# ControllerESP32.net
KiCad netlist of a schematic drawn in EAGLE
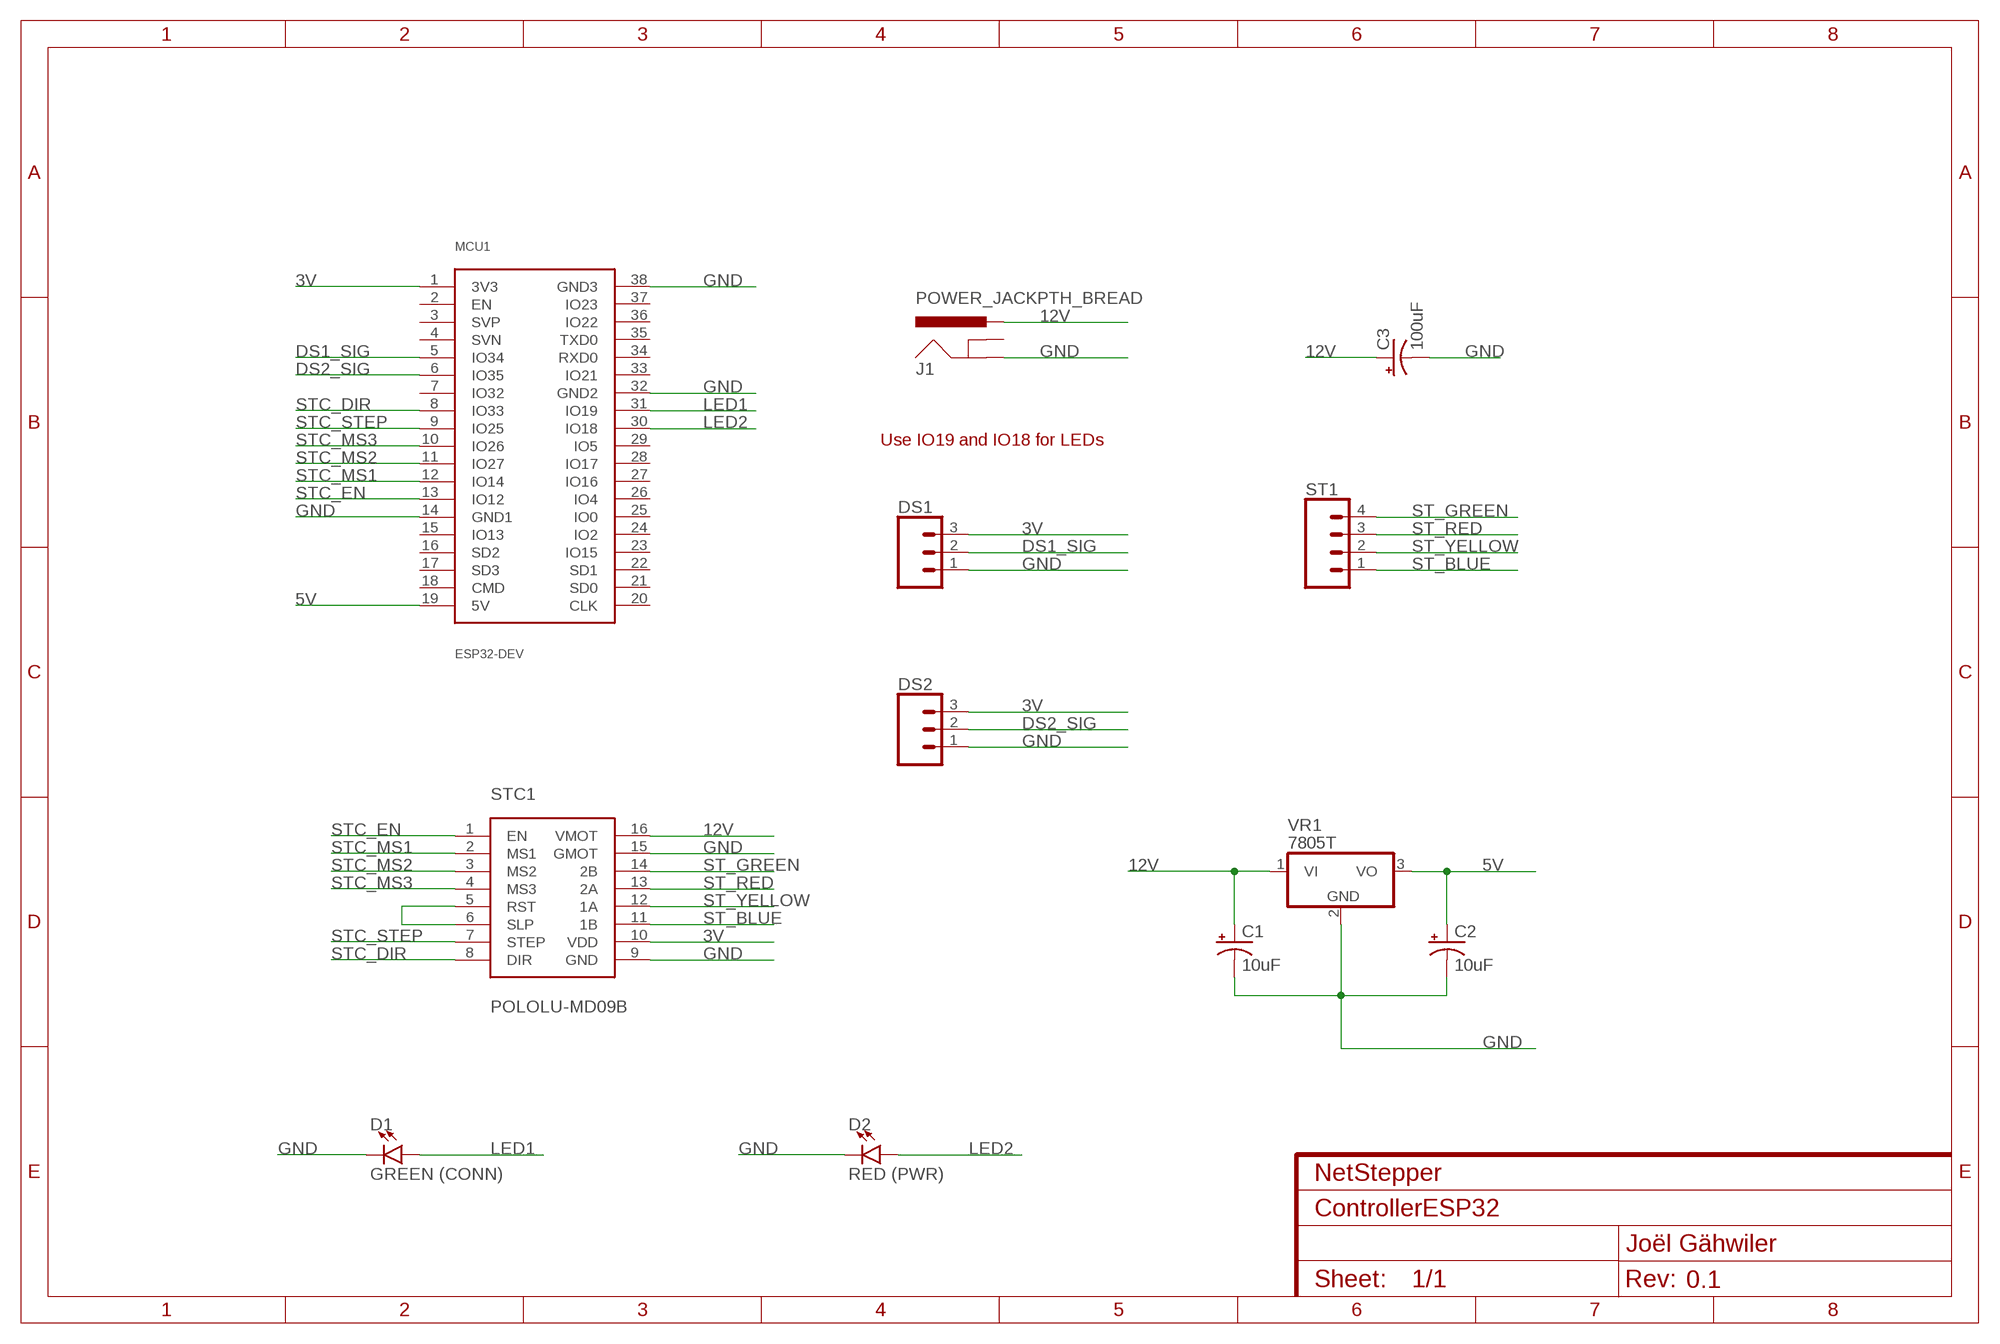
[diagram p0: schematic, sheet 1]

(export (version "E")
  (design (tool "Eeschema 10.0.6"))
  (components
    (comp (ref "C1")
      (value "10uF")
      (footprint "eagle-import:E2-5")
      (libsource (lib "eagle-import") (part "CPOL-USE2-5"))
    )
    (comp (ref "C2")
      (value "10uF")
      (footprint "eagle-import:E2-5")
      (libsource (lib "eagle-import") (part "CPOL-USE2-5"))
    )
    (comp (ref "C3")
      (value "100uF")
      (footprint "eagle-import:E2-5")
      (libsource (lib "eagle-import") (part "CPOL-USE2-5"))
    )
    (comp (ref "D1")
      (value "GREEN (CONN)")
      (footprint "eagle-import:LED_5MM")
      (libsource (lib "eagle-import") (part "LED5MM"))
    )
    (comp (ref "D2")
      (value "RED (PWR)")
      (footprint "eagle-import:LED_5MM")
      (libsource (lib "eagle-import") (part "LED5MM"))
    )
    (comp (ref "DS1")
      (value "CONN_03LONGPADS")
      (footprint "eagle-import:1X03_LONGPADS")
      (libsource (lib "eagle-import") (part "CONN_03LONGPADS"))
    )
    (comp (ref "DS2")
      (value "CONN_03LONGPADS")
      (footprint "eagle-import:1X03_LONGPADS")
      (libsource (lib "eagle-import") (part "CONN_03LONGPADS"))
    )
    (comp (ref "J1")
      (value "POWER_JACKPTH_BREAD")
      (footprint "eagle-import:POWER_JACK_PTH_BREAD")
      (libsource (lib "eagle-import") (part "POWER_JACKPTH_BREAD"))
    )
    (comp (ref "MCU1")
      (value "ESP32-DEV")
      (footprint "eagle-import:ESP32-DEV")
      (libsource (lib "eagle-import") (part "ESP32-DEV"))
    )
    (comp (ref "ST1")
      (value "CONN_04LONGPADS")
      (footprint "eagle-import:1X04_LONGPADS")
      (libsource (lib "eagle-import") (part "CONN_04LONGPADS"))
    )
    (comp (ref "STC1")
      (value "POLOLU-MD09B")
      (footprint "eagle-import:POLOLU-MD09B")
      (libsource (lib "eagle-import") (part "POLOLU-MD09B"))
    )
    (comp (ref "VR1")
      (value "7805T")
      (footprint "eagle-import:TO220H")
      (libsource (lib "eagle-import") (part "78T05"))
    )
  )
  (nets
    (net (code "1") (name "/3V") (class "Default")
      (node (ref "DS1") (pin "3") (pinfunction "3_3") (pintype "passive"))
      (node (ref "DS2") (pin "3") (pinfunction "3_3") (pintype "passive"))
      (node (ref "MCU1") (pin "1") (pinfunction "3V3_1") (pintype "bidirectional"))
      (node (ref "STC1") (pin "10") (pinfunction "VDD_10") (pintype "bidirectional"))
    )
    (net (code "2") (name "/5V") (class "Default")
      (node (ref "C2") (pin "+") (pinfunction "+_+") (pintype "passive"))
      (node (ref "MCU1") (pin "19") (pinfunction "5V_19") (pintype "bidirectional"))
      (node (ref "VR1") (pin "3") (pinfunction "VO_3") (pintype "passive"))
    )
    (net (code "3") (name "/12V") (class "Default")
      (node (ref "C1") (pin "+") (pinfunction "+_+") (pintype "passive"))
      (node (ref "C3") (pin "+") (pinfunction "+_+") (pintype "passive"))
      (node (ref "J1") (pin "PWR") (pinfunction "PWR_PWR") (pintype "bidirectional"))
      (node (ref "STC1") (pin "16") (pinfunction "VMOT_16") (pintype "bidirectional"))
      (node (ref "VR1") (pin "1") (pinfunction "VI_1") (pintype "input"))
    )
    (net (code "4") (name "/DS1_SIG") (class "Default")
      (node (ref "DS1") (pin "2") (pinfunction "2_2") (pintype "passive"))
      (node (ref "MCU1") (pin "5") (pinfunction "IO34_5") (pintype "bidirectional"))
    )
    (net (code "5") (name "/DS2_SIG") (class "Default")
      (node (ref "DS2") (pin "2") (pinfunction "2_2") (pintype "passive"))
      (node (ref "MCU1") (pin "6") (pinfunction "IO35_6") (pintype "bidirectional"))
    )
    (net (code "6") (name "/GND") (class "Default")
      (node (ref "C1") (pin "-") (pinfunction "-_-") (pintype "passive"))
      (node (ref "C2") (pin "-") (pinfunction "-_-") (pintype "passive"))
      (node (ref "C3") (pin "-") (pinfunction "-_-") (pintype "passive"))
      (node (ref "D1") (pin "K") (pinfunction "C_K") (pintype "passive"))
      (node (ref "D2") (pin "K") (pinfunction "C_K") (pintype "passive"))
      (node (ref "DS1") (pin "1") (pinfunction "1_1") (pintype "passive"))
      (node (ref "DS2") (pin "1") (pinfunction "1_1") (pintype "passive"))
      (node (ref "J1") (pin "GND") (pinfunction "GND_GND") (pintype "bidirectional"))
      (node (ref "MCU1") (pin "14") (pinfunction "GND1_14") (pintype "bidirectional"))
      (node (ref "MCU1") (pin "32") (pinfunction "GND2_32") (pintype "bidirectional"))
      (node (ref "MCU1") (pin "38") (pinfunction "GND3_38") (pintype "bidirectional"))
      (node (ref "STC1") (pin "15") (pinfunction "GMOT_15") (pintype "bidirectional"))
      (node (ref "STC1") (pin "9") (pinfunction "GND_9") (pintype "bidirectional"))
      (node (ref "VR1") (pin "2") (pinfunction "GND_2") (pintype "passive"))
    )
    (net (code "7") (name "/LED1") (class "Default")
      (node (ref "D1") (pin "A") (pinfunction "A_A") (pintype "passive"))
      (node (ref "MCU1") (pin "31") (pinfunction "IO19_31") (pintype "bidirectional"))
    )
    (net (code "8") (name "/LED2") (class "Default")
      (node (ref "D2") (pin "A") (pinfunction "A_A") (pintype "passive"))
      (node (ref "MCU1") (pin "30") (pinfunction "IO18_30") (pintype "bidirectional"))
    )
    (net (code "9") (name "/STC_DIR") (class "Default")
      (node (ref "MCU1") (pin "8") (pinfunction "IO33_8") (pintype "bidirectional"))
      (node (ref "STC1") (pin "8") (pinfunction "DIR_8") (pintype "bidirectional"))
    )
    (net (code "10") (name "/STC_EN") (class "Default")
      (node (ref "MCU1") (pin "13") (pinfunction "IO12_13") (pintype "bidirectional"))
      (node (ref "STC1") (pin "1") (pinfunction "EN_1") (pintype "bidirectional"))
    )
    (net (code "11") (name "/STC_MS1") (class "Default")
      (node (ref "MCU1") (pin "12") (pinfunction "IO14_12") (pintype "bidirectional"))
      (node (ref "STC1") (pin "2") (pinfunction "MS1_2") (pintype "bidirectional"))
    )
    (net (code "12") (name "/STC_MS2") (class "Default")
      (node (ref "MCU1") (pin "11") (pinfunction "IO27_11") (pintype "bidirectional"))
      (node (ref "STC1") (pin "3") (pinfunction "MS2_3") (pintype "bidirectional"))
    )
    (net (code "13") (name "/STC_MS3") (class "Default")
      (node (ref "MCU1") (pin "10") (pinfunction "IO26_10") (pintype "bidirectional"))
      (node (ref "STC1") (pin "4") (pinfunction "MS3_4") (pintype "bidirectional"))
    )
    (net (code "14") (name "/STC_STEP") (class "Default")
      (node (ref "MCU1") (pin "9") (pinfunction "IO25_9") (pintype "bidirectional"))
      (node (ref "STC1") (pin "7") (pinfunction "STEP_7") (pintype "bidirectional"))
    )
    (net (code "15") (name "/ST_BLUE") (class "Default")
      (node (ref "ST1") (pin "1") (pinfunction "1_1") (pintype "passive"))
      (node (ref "STC1") (pin "11") (pinfunction "1B_11") (pintype "bidirectional"))
    )
    (net (code "16") (name "/ST_GREEN") (class "Default")
      (node (ref "ST1") (pin "4") (pinfunction "4_4") (pintype "passive"))
      (node (ref "STC1") (pin "14") (pinfunction "2B_14") (pintype "bidirectional"))
    )
    (net (code "17") (name "/ST_RED") (class "Default")
      (node (ref "ST1") (pin "3") (pinfunction "3_3") (pintype "passive"))
      (node (ref "STC1") (pin "13") (pinfunction "2A_13") (pintype "bidirectional"))
    )
    (net (code "18") (name "/ST_YELLOW") (class "Default")
      (node (ref "ST1") (pin "2") (pinfunction "2_2") (pintype "passive"))
      (node (ref "STC1") (pin "12") (pinfunction "1A_12") (pintype "bidirectional"))
    )
    (net (code "19") (name "Net-(STC1-RST)") (class "Default")
      (node (ref "STC1") (pin "5") (pinfunction "RST_5") (pintype "bidirectional"))
      (node (ref "STC1") (pin "6") (pinfunction "SLP_6") (pintype "bidirectional"))
    )
    (net (code "20") (name "unconnected-(J1-PadGNDBREAK)") (class "Default")
      (node (ref "J1") (pin "GNDBREAK") (pinfunction "GNDBREAK_GNDBREAK") (pintype "bidirectional"))
    )
    (net (code "21") (name "unconnected-(MCU1-CLK-Pad20)") (class "Default")
      (node (ref "MCU1") (pin "20") (pinfunction "CLK_20") (pintype "bidirectional"))
    )
    (net (code "22") (name "unconnected-(MCU1-CMD-Pad18)") (class "Default")
      (node (ref "MCU1") (pin "18") (pinfunction "CMD_18") (pintype "bidirectional"))
    )
    (net (code "23") (name "unconnected-(MCU1-EN-Pad2)") (class "Default")
      (node (ref "MCU1") (pin "2") (pinfunction "EN_2") (pintype "bidirectional"))
    )
    (net (code "24") (name "unconnected-(MCU1-IO0-Pad25)") (class "Default")
      (node (ref "MCU1") (pin "25") (pinfunction "IO0_25") (pintype "bidirectional"))
    )
    (net (code "25") (name "unconnected-(MCU1-IO2-Pad24)") (class "Default")
      (node (ref "MCU1") (pin "24") (pinfunction "IO2_24") (pintype "bidirectional"))
    )
    (net (code "26") (name "unconnected-(MCU1-IO4-Pad26)") (class "Default")
      (node (ref "MCU1") (pin "26") (pinfunction "IO4_26") (pintype "bidirectional"))
    )
    (net (code "27") (name "unconnected-(MCU1-IO5-Pad29)") (class "Default")
      (node (ref "MCU1") (pin "29") (pinfunction "IO5_29") (pintype "bidirectional"))
    )
    (net (code "28") (name "unconnected-(MCU1-IO13-Pad15)") (class "Default")
      (node (ref "MCU1") (pin "15") (pinfunction "IO13_15") (pintype "bidirectional"))
    )
    (net (code "29") (name "unconnected-(MCU1-IO15-Pad23)") (class "Default")
      (node (ref "MCU1") (pin "23") (pinfunction "IO15_23") (pintype "bidirectional"))
    )
    (net (code "30") (name "unconnected-(MCU1-IO16-Pad27)") (class "Default")
      (node (ref "MCU1") (pin "27") (pinfunction "IO16_27") (pintype "bidirectional"))
    )
    (net (code "31") (name "unconnected-(MCU1-IO17-Pad28)") (class "Default")
      (node (ref "MCU1") (pin "28") (pinfunction "IO17_28") (pintype "bidirectional"))
    )
    (net (code "32") (name "unconnected-(MCU1-IO21-Pad33)") (class "Default")
      (node (ref "MCU1") (pin "33") (pinfunction "IO21_33") (pintype "bidirectional"))
    )
    (net (code "33") (name "unconnected-(MCU1-IO22-Pad36)") (class "Default")
      (node (ref "MCU1") (pin "36") (pinfunction "IO22_36") (pintype "bidirectional"))
    )
    (net (code "34") (name "unconnected-(MCU1-IO23-Pad37)") (class "Default")
      (node (ref "MCU1") (pin "37") (pinfunction "IO23_37") (pintype "bidirectional"))
    )
    (net (code "35") (name "unconnected-(MCU1-IO32-Pad7)") (class "Default")
      (node (ref "MCU1") (pin "7") (pinfunction "IO32_7") (pintype "bidirectional"))
    )
    (net (code "36") (name "unconnected-(MCU1-RXD0-Pad34)") (class "Default")
      (node (ref "MCU1") (pin "34") (pinfunction "RXD0_34") (pintype "bidirectional"))
    )
    (net (code "37") (name "unconnected-(MCU1-SD0-Pad21)") (class "Default")
      (node (ref "MCU1") (pin "21") (pinfunction "SD0_21") (pintype "bidirectional"))
    )
    (net (code "38") (name "unconnected-(MCU1-SD1-Pad22)") (class "Default")
      (node (ref "MCU1") (pin "22") (pinfunction "SD1_22") (pintype "bidirectional"))
    )
    (net (code "39") (name "unconnected-(MCU1-SD2-Pad16)") (class "Default")
      (node (ref "MCU1") (pin "16") (pinfunction "SD2_16") (pintype "bidirectional"))
    )
    (net (code "40") (name "unconnected-(MCU1-SD3-Pad17)") (class "Default")
      (node (ref "MCU1") (pin "17") (pinfunction "SD3_17") (pintype "bidirectional"))
    )
    (net (code "41") (name "unconnected-(MCU1-SVN-Pad4)") (class "Default")
      (node (ref "MCU1") (pin "4") (pinfunction "SVN_4") (pintype "bidirectional"))
    )
    (net (code "42") (name "unconnected-(MCU1-SVP-Pad3)") (class "Default")
      (node (ref "MCU1") (pin "3") (pinfunction "SVP_3") (pintype "bidirectional"))
    )
    (net (code "43") (name "unconnected-(MCU1-TXD0-Pad35)") (class "Default")
      (node (ref "MCU1") (pin "35") (pinfunction "TXD0_35") (pintype "bidirectional"))
    )
  )
)
